# cerebroICSP1_2.net
KiCad netlist of a schematic drawn in EAGLE
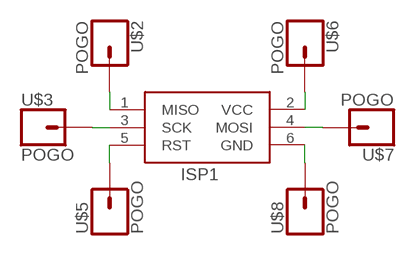
[diagram p0: schematic, sheet 1]

(export (version "E")
  (design (tool "Eeschema 10.0.6"))
  (components
    (comp (ref "ISP1")
      (value "AVRISP-BOX")
      (footprint "eagle-import:AVRISP-BOX")
      (libsource (lib "eagle-import") (part "AVRISP-BOX"))
    )
    (comp (ref "U$2")
      (value "POGO")
      (footprint "eagle-import:POGO")
      (libsource (lib "eagle-import") (part "POGO"))
    )
    (comp (ref "U$3")
      (value "POGO")
      (footprint "eagle-import:POGO")
      (libsource (lib "eagle-import") (part "POGO"))
    )
    (comp (ref "U$5")
      (value "POGO")
      (footprint "eagle-import:POGO")
      (libsource (lib "eagle-import") (part "POGO"))
    )
    (comp (ref "U$6")
      (value "POGO")
      (footprint "eagle-import:POGO")
      (libsource (lib "eagle-import") (part "POGO"))
    )
    (comp (ref "U$7")
      (value "POGO")
      (footprint "eagle-import:POGO")
      (libsource (lib "eagle-import") (part "POGO"))
    )
    (comp (ref "U$8")
      (value "POGO")
      (footprint "eagle-import:POGO")
      (libsource (lib "eagle-import") (part "POGO"))
    )
  )
  (nets
    (net (code "1") (name "Net-(ISP1-GND)") (class "Default")
      (node (ref "ISP1") (pin "6") (pinfunction "GND_6") (pintype "power_in"))
      (node (ref "U$8") (pin "P$1") (pinfunction "1_P$1") (pintype "passive"))
    )
    (net (code "2") (name "Net-(ISP1-MISO)") (class "Default")
      (node (ref "ISP1") (pin "1") (pinfunction "MISO_1") (pintype "input"))
      (node (ref "U$2") (pin "P$1") (pinfunction "1_P$1") (pintype "passive"))
    )
    (net (code "3") (name "Net-(ISP1-MOSI)") (class "Default")
      (node (ref "ISP1") (pin "4") (pinfunction "MOSI_4") (pintype "output"))
      (node (ref "U$7") (pin "P$1") (pinfunction "1_P$1") (pintype "passive"))
    )
    (net (code "4") (name "Net-(ISP1-RST)") (class "Default")
      (node (ref "ISP1") (pin "5") (pinfunction "RST_5") (pintype "output"))
      (node (ref "U$5") (pin "P$1") (pinfunction "1_P$1") (pintype "passive"))
    )
    (net (code "5") (name "Net-(ISP1-SCK)") (class "Default")
      (node (ref "ISP1") (pin "3") (pinfunction "SCK_3") (pintype "output"))
      (node (ref "U$3") (pin "P$1") (pinfunction "1_P$1") (pintype "passive"))
    )
    (net (code "6") (name "Net-(ISP1-VCC)") (class "Default")
      (node (ref "ISP1") (pin "2") (pinfunction "VCC_2") (pintype "power_in"))
      (node (ref "U$6") (pin "P$1") (pinfunction "1_P$1") (pintype "passive"))
    )
  )
)
